# ShuntTest_2.net
KiCad netlist of a schematic drawn in EAGLE
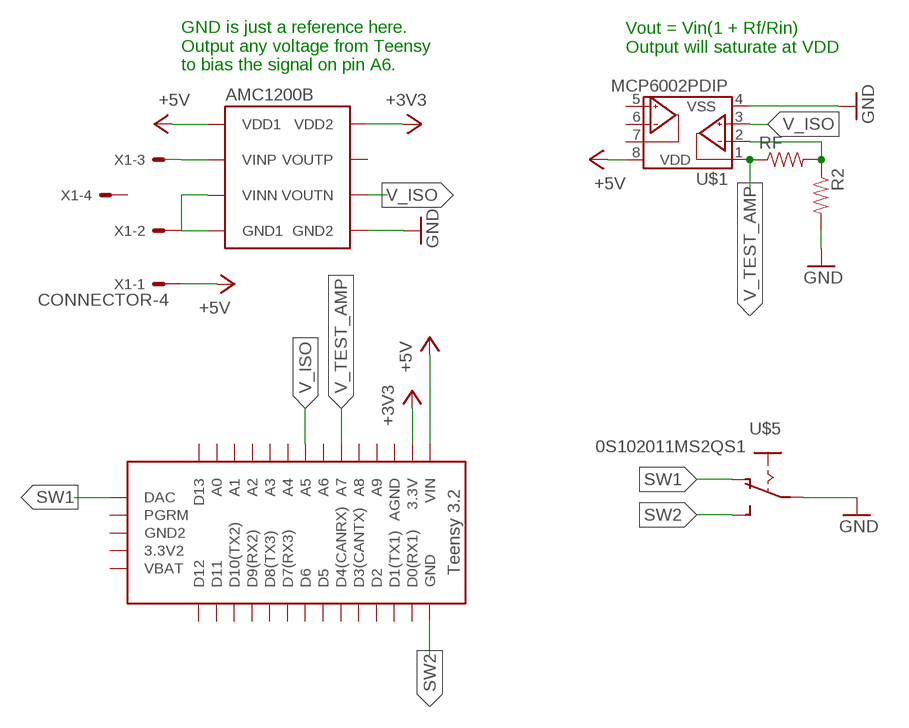
[diagram p0: schematic, sheet 1]

(export (version "E")
  (design (tool "Eeschema 10.0.6"))
  (components
    (comp (ref "R2")
      (value "RESISTOR0402")
      (footprint "eagle-import:0402-RES")
      (libsource (lib "eagle-import") (part "RESISTOR0402"))
    )
    (comp (ref "RF")
      (value "RESISTOR0402")
      (footprint "eagle-import:0402-RES")
      (libsource (lib "eagle-import") (part "RESISTOR0402"))
    )
    (comp (ref "U$1")
      (value "MCP6002PDIP")
      (footprint "eagle-import:DIL08")
      (libsource (lib "eagle-import") (part "MCP6002PDIP"))
    )
    (comp (ref "U$2")
      (value "TEENSY_3.2_EXT")
      (footprint "eagle-import:TEENSY_3.2_EXT")
      (libsource (lib "eagle-import") (part "TEENSY_3.2_EXT"))
    )
    (comp (ref "U$3")
      (value "AMC1200B")
      (footprint "eagle-import:AMC1200B")
      (libsource (lib "eagle-import") (part "AMC1200B"))
    )
    (comp (ref "U$5")
      (value "0S102011MS2QS1")
      (footprint "eagle-import:0S102011MS2QS1")
      (libsource (lib "eagle-import") (part "0S102011MS2QS1"))
    )
    (comp (ref "X1")
      (value "CONNECTOR-4")
      (footprint "eagle-import:MINIFIT_5566-4")
      (libsource (lib "eagle-import") (part "CONNECTOR-4"))
    )
  )
  (nets
    (net (code "1") (name "+3V3") (class "Default")
      (node (ref "U$2") (pin "3.3V") (pinfunction "3.3V_3.3V") (pintype "bidirectional"))
      (node (ref "U$3") (pin "VDD2") (pinfunction "VDD2_VDD2") (pintype "power_in"))
    )
    (net (code "2") (name "+5V") (class "Default")
      (node (ref "U$1") (pin "8") (pinfunction "VDD_8") (pintype "passive"))
      (node (ref "U$2") (pin "VIN") (pinfunction "VIN_VIN") (pintype "bidirectional"))
      (node (ref "U$3") (pin "VDD1") (pinfunction "VDD1_VDD1") (pintype "power_in"))
      (node (ref "X1") (pin "1") (pinfunction "S_1") (pintype "passive"))
    )
    (net (code "3") (name "GND") (class "Default")
      (node (ref "R2") (pin "2") (pinfunction "2_2") (pintype "passive"))
      (node (ref "U$1") (pin "4") (pinfunction "VSS_4") (pintype "passive"))
      (node (ref "U$3") (pin "GND2") (pinfunction "GND2_GND2") (pintype "power_in"))
      (node (ref "U$5") (pin "P$2") (pinfunction "P_P$2") (pintype "passive"))
    )
    (net (code "4") (name "Net-(U$1-VINA-)") (class "Default")
      (node (ref "R2") (pin "1") (pinfunction "1_1") (pintype "passive"))
      (node (ref "RF") (pin "2") (pinfunction "2_2") (pintype "passive"))
      (node (ref "U$1") (pin "2") (pinfunction "VINA-_2") (pintype "passive"))
    )
    (net (code "5") (name "Net-(X1B-S)") (class "Default")
      (node (ref "U$3") (pin "GND1") (pinfunction "GND1_GND1") (pintype "power_in"))
      (node (ref "U$3") (pin "VINN") (pinfunction "VINN_VINN") (pintype "input"))
      (node (ref "X1") (pin "2") (pinfunction "S_2") (pintype "passive"))
    )
    (net (code "6") (name "Net-(X1C-S)") (class "Default")
      (node (ref "U$3") (pin "VINP") (pinfunction "VINP_VINP") (pintype "input"))
      (node (ref "X1") (pin "3") (pinfunction "S_3") (pintype "passive"))
    )
    (net (code "7") (name "SW1") (class "Default")
      (node (ref "U$2") (pin "DAC") (pinfunction "DAC_DAC") (pintype "bidirectional"))
      (node (ref "U$5") (pin "P$1") (pinfunction "O_P$1") (pintype "passive"))
    )
    (net (code "8") (name "SW2") (class "Default")
      (node (ref "U$2") (pin "GND") (pinfunction "GND_GND") (pintype "bidirectional"))
      (node (ref "U$5") (pin "P$3") (pinfunction "S_P$3") (pintype "passive"))
    )
    (net (code "9") (name "V_ISO") (class "Default")
      (node (ref "U$1") (pin "3") (pinfunction "VINA+_3") (pintype "passive"))
      (node (ref "U$2") (pin "A5") (pinfunction "A5_A5") (pintype "bidirectional"))
      (node (ref "U$3") (pin "VOUTN") (pinfunction "VOUTN_VOUTN") (pintype "output"))
    )
    (net (code "10") (name "V_TEST_AMP") (class "Default")
      (node (ref "RF") (pin "1") (pinfunction "1_1") (pintype "passive"))
      (node (ref "U$1") (pin "1") (pinfunction "VOUTA_1") (pintype "passive"))
      (node (ref "U$2") (pin "A7") (pinfunction "A7_A7") (pintype "bidirectional"))
    )
    (net (code "11") (name "unconnected-(U$1-VINB+-Pad5)") (class "Default")
      (node (ref "U$1") (pin "5") (pinfunction "VINB+_5") (pintype "passive"))
    )
    (net (code "12") (name "unconnected-(U$1-VINB--Pad6)") (class "Default")
      (node (ref "U$1") (pin "6") (pinfunction "VINB-_6") (pintype "passive"))
    )
    (net (code "13") (name "unconnected-(U$1-VOUTB-Pad7)") (class "Default")
      (node (ref "U$1") (pin "7") (pinfunction "VOUTB_7") (pintype "passive"))
    )
    (net (code "14") (name "unconnected-(U$2-Pad3.3V2)") (class "Default")
      (node (ref "U$2") (pin "3.3V2") (pinfunction "3.3V2_3.3V2") (pintype "bidirectional"))
    )
    (net (code "15") (name "unconnected-(U$2-PadA0)") (class "Default")
      (node (ref "U$2") (pin "A0") (pinfunction "A0_A0") (pintype "bidirectional"))
    )
    (net (code "16") (name "unconnected-(U$2-PadA1)") (class "Default")
      (node (ref "U$2") (pin "A1") (pinfunction "A1_A1") (pintype "bidirectional"))
    )
    (net (code "17") (name "unconnected-(U$2-PadA2)") (class "Default")
      (node (ref "U$2") (pin "A2") (pinfunction "A2_A2") (pintype "bidirectional"))
    )
    (net (code "18") (name "unconnected-(U$2-PadA3)") (class "Default")
      (node (ref "U$2") (pin "A3") (pinfunction "A3_A3") (pintype "bidirectional"))
    )
    (net (code "19") (name "unconnected-(U$2-PadA4)") (class "Default")
      (node (ref "U$2") (pin "A4") (pinfunction "A4_A4") (pintype "bidirectional"))
    )
    (net (code "20") (name "unconnected-(U$2-PadA6)") (class "Default")
      (node (ref "U$2") (pin "A6") (pinfunction "A6_A6") (pintype "bidirectional"))
    )
    (net (code "21") (name "unconnected-(U$2-PadA8)") (class "Default")
      (node (ref "U$2") (pin "A8") (pinfunction "A8_A8") (pintype "bidirectional"))
    )
    (net (code "22") (name "unconnected-(U$2-PadA9)") (class "Default")
      (node (ref "U$2") (pin "A9") (pinfunction "A9_A9") (pintype "bidirectional"))
    )
    (net (code "23") (name "unconnected-(U$2-PadAGND)") (class "Default")
      (node (ref "U$2") (pin "AGND") (pinfunction "AGND_AGND") (pintype "bidirectional"))
    )
    (net (code "24") (name "unconnected-(U$2-PadD0(RX1))") (class "Default")
      (node (ref "U$2") (pin "D0(RX1)") (pinfunction "D0(RX1)_D0(RX1)") (pintype "bidirectional"))
    )
    (net (code "25") (name "unconnected-(U$2-PadD1(TX1))") (class "Default")
      (node (ref "U$2") (pin "D1(TX1)") (pinfunction "D1(TX1)_D1(TX1)") (pintype "bidirectional"))
    )
    (net (code "26") (name "unconnected-(U$2-PadD2)") (class "Default")
      (node (ref "U$2") (pin "D2") (pinfunction "D2_D2") (pintype "bidirectional"))
    )
    (net (code "27") (name "unconnected-(U$2-PadD3(CANTX))") (class "Default")
      (node (ref "U$2") (pin "D3(CANTX)") (pinfunction "D3(CANTX)_D3(CANTX)") (pintype "bidirectional"))
    )
    (net (code "28") (name "unconnected-(U$2-PadD4(CANRX))") (class "Default")
      (node (ref "U$2") (pin "D4(CANRX)") (pinfunction "D4(CANRX)_D4(CANRX)") (pintype "bidirectional"))
    )
    (net (code "29") (name "unconnected-(U$2-PadD5)") (class "Default")
      (node (ref "U$2") (pin "D5") (pinfunction "D5_D5") (pintype "bidirectional"))
    )
    (net (code "30") (name "unconnected-(U$2-PadD6)") (class "Default")
      (node (ref "U$2") (pin "D6") (pinfunction "D6_D6") (pintype "bidirectional"))
    )
    (net (code "31") (name "unconnected-(U$2-PadD7(RX3))") (class "Default")
      (node (ref "U$2") (pin "D7(RX3)") (pinfunction "D7(RX3)_D7(RX3)") (pintype "bidirectional"))
    )
    (net (code "32") (name "unconnected-(U$2-PadD8(TX3))") (class "Default")
      (node (ref "U$2") (pin "D8(TX3)") (pinfunction "D8(TX3)_D8(TX3)") (pintype "bidirectional"))
    )
    (net (code "33") (name "unconnected-(U$2-PadD9(RX2))") (class "Default")
      (node (ref "U$2") (pin "D9(RX2)") (pinfunction "D9(RX2)_D9(RX2)") (pintype "bidirectional"))
    )
    (net (code "34") (name "unconnected-(U$2-PadD10(TX2))") (class "Default")
      (node (ref "U$2") (pin "D10(TX2)") (pinfunction "D10(TX2)_D10(TX2)") (pintype "bidirectional"))
    )
    (net (code "35") (name "unconnected-(U$2-PadD11)") (class "Default")
      (node (ref "U$2") (pin "D11") (pinfunction "D11_D11") (pintype "bidirectional"))
    )
    (net (code "36") (name "unconnected-(U$2-PadD12)") (class "Default")
      (node (ref "U$2") (pin "D12") (pinfunction "D12_D12") (pintype "bidirectional"))
    )
    (net (code "37") (name "unconnected-(U$2-PadD13)") (class "Default")
      (node (ref "U$2") (pin "D13") (pinfunction "D13_D13") (pintype "bidirectional"))
    )
    (net (code "38") (name "unconnected-(U$2-PadGND2)") (class "Default")
      (node (ref "U$2") (pin "GND2") (pinfunction "GND2_GND2") (pintype "bidirectional"))
    )
    (net (code "39") (name "unconnected-(U$2-PadPGRM)") (class "Default")
      (node (ref "U$2") (pin "PGRM") (pinfunction "PGRM_PGRM") (pintype "bidirectional"))
    )
    (net (code "40") (name "unconnected-(U$2-PadVBAT)") (class "Default")
      (node (ref "U$2") (pin "VBAT") (pinfunction "VBAT_VBAT") (pintype "bidirectional"))
    )
    (net (code "41") (name "unconnected-(U$3-PadVOUTP)") (class "Default")
      (node (ref "U$3") (pin "VOUTP") (pinfunction "VOUTP_VOUTP") (pintype "output"))
    )
    (net (code "42") (name "unconnected-(X1D-S-Pad4)") (class "Default")
      (node (ref "X1") (pin "4") (pinfunction "S_4") (pintype "passive"))
    )
  )
)
